# MAG3110_Breakout.net
KiCad netlist of a schematic drawn in EAGLE
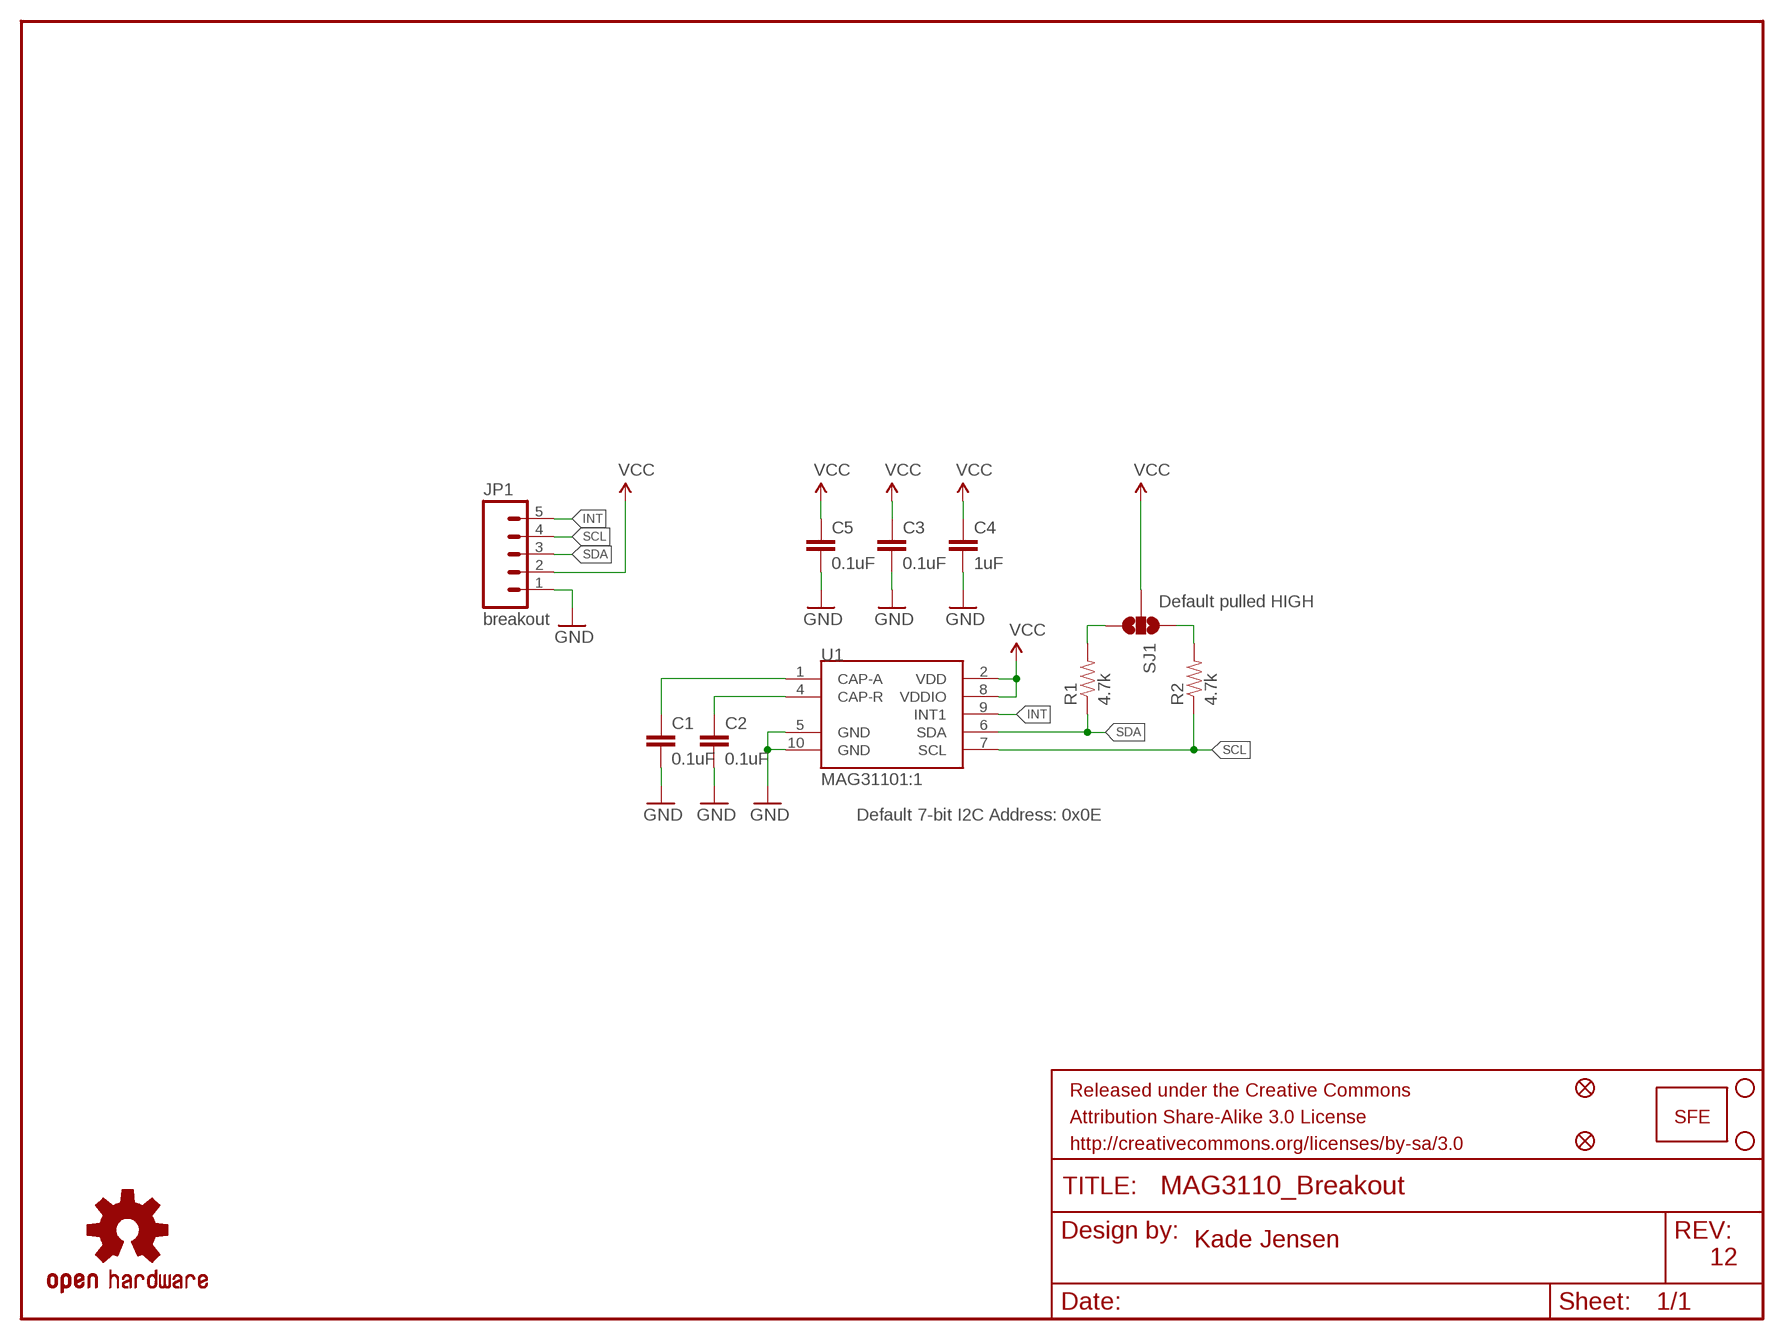
[diagram p0: schematic, sheet 1]

(export (version "E")
  (design (tool "Eeschema 10.0.6"))
  (components
    (comp (ref "C1")
      (value "0.1uF")
      (footprint "eagle-import:0603-CAP")
      (libsource (lib "eagle-import") (part "CAP0603-CAP"))
    )
    (comp (ref "C2")
      (value "0.1uF")
      (footprint "eagle-import:0603-CAP")
      (libsource (lib "eagle-import") (part "CAP0603-CAP"))
    )
    (comp (ref "C3")
      (value "0.1uF")
      (footprint "eagle-import:0603-CAP")
      (libsource (lib "eagle-import") (part "CAP0603-CAP"))
    )
    (comp (ref "C4")
      (value "1uF")
      (footprint "eagle-import:0603-CAP")
      (libsource (lib "eagle-import") (part "CAP0603-CAP"))
    )
    (comp (ref "C5")
      (value "0.1uF")
      (footprint "eagle-import:0603-CAP")
      (libsource (lib "eagle-import") (part "CAP0603-CAP"))
    )
    (comp (ref "FID1")
      (value "FIDUCIAL1X2")
      (footprint "eagle-import:FIDUCIAL-1X2")
      (libsource (lib "eagle-import") (part "FIDUCIAL1X2"))
    )
    (comp (ref "FID2")
      (value "FIDUCIAL1X2")
      (footprint "eagle-import:FIDUCIAL-1X2")
      (libsource (lib "eagle-import") (part "FIDUCIAL1X2"))
    )
    (comp (ref "FRAME2")
      (value "FRAME-LETTER")
      (footprint "eagle-import:CREATIVE_COMMONS")
      (libsource (lib "eagle-import") (part "FRAME-LETTER"))
    )
    (comp (ref "JP1")
      (value "breakout")
      (footprint "eagle-import:1X05")
      (libsource (lib "eagle-import") (part "M05PTH"))
    )
    (comp (ref "JP2")
      (value "STAND-OFF")
      (footprint "eagle-import:STAND-OFF")
      (libsource (lib "eagle-import") (part "STAND-OFF"))
    )
    (comp (ref "JP3")
      (value "STAND-OFF")
      (footprint "eagle-import:STAND-OFF")
      (libsource (lib "eagle-import") (part "STAND-OFF"))
    )
    (comp (ref "JP7")
      (value "LOGO-SFESK")
      (footprint "eagle-import:SFE-LOGO-FLAME")
      (libsource (lib "eagle-import") (part "LOGO-SFESK"))
    )
    (comp (ref "LOGO1")
      (value "OSHW-LOGOS")
      (footprint "eagle-import:OSHW-LOGO-S")
      (libsource (lib "eagle-import") (part "OSHW-LOGOS"))
    )
    (comp (ref "R1")
      (value "4.7k")
      (footprint "eagle-import:0603-RES")
      (libsource (lib "eagle-import") (part "RESISTOR0603-RES"))
    )
    (comp (ref "R2")
      (value "4.7k")
      (footprint "eagle-import:0603-RES")
      (libsource (lib "eagle-import") (part "RESISTOR0603-RES"))
    )
    (comp (ref "SJ1")
      (value "SOLDERJUMPER_2WAYPASTE1&2&3")
      (footprint "eagle-import:SJ_3_PASTE1&2&3")
      (libsource (lib "eagle-import") (part "SOLDERJUMPER_2WAYPASTE1&2&3"))
    )
    (comp (ref "U1")
      (value "MAG31101:1")
      (footprint "eagle-import:DFN-10-W")
      (libsource (lib "eagle-import") (part "MAG31101{colon}1"))
    )
  )
  (nets
    (net (code "1") (name "GND") (class "Default")
      (node (ref "C1") (pin "2") (pinfunction "2_2") (pintype "passive"))
      (node (ref "C2") (pin "2") (pinfunction "2_2") (pintype "passive"))
      (node (ref "C3") (pin "2") (pinfunction "2_2") (pintype "passive"))
      (node (ref "C4") (pin "2") (pinfunction "2_2") (pintype "passive"))
      (node (ref "C5") (pin "2") (pinfunction "2_2") (pintype "passive"))
      (node (ref "JP1") (pin "1") (pinfunction "1_1") (pintype "passive"))
      (node (ref "U1") (pin "10") (pinfunction "GND_10") (pintype "bidirectional"))
      (node (ref "U1") (pin "5") (pinfunction "GND_5") (pintype "bidirectional"))
    )
    (net (code "2") (name "INT") (class "Default")
      (node (ref "JP1") (pin "5") (pinfunction "5_5") (pintype "passive"))
      (node (ref "U1") (pin "9") (pinfunction "INT1_9") (pintype "bidirectional"))
    )
    (net (code "3") (name "Net-(R1-Pad2)") (class "Default")
      (node (ref "R1") (pin "2") (pinfunction "2_2") (pintype "passive"))
      (node (ref "SJ1") (pin "3") (pinfunction "3_3") (pintype "passive"))
    )
    (net (code "4") (name "Net-(R2-Pad2)") (class "Default")
      (node (ref "R2") (pin "2") (pinfunction "2_2") (pintype "passive"))
      (node (ref "SJ1") (pin "1") (pinfunction "1_1") (pintype "passive"))
    )
    (net (code "5") (name "Net-(U1-CAP-A)") (class "Default")
      (node (ref "C1") (pin "1") (pinfunction "1_1") (pintype "passive"))
      (node (ref "U1") (pin "1") (pinfunction "CAP-A_1") (pintype "bidirectional"))
    )
    (net (code "6") (name "Net-(U1-CAP-R)") (class "Default")
      (node (ref "C2") (pin "1") (pinfunction "1_1") (pintype "passive"))
      (node (ref "U1") (pin "4") (pinfunction "CAP-R_4") (pintype "bidirectional"))
    )
    (net (code "7") (name "SCL") (class "Default")
      (node (ref "JP1") (pin "4") (pinfunction "4_4") (pintype "passive"))
      (node (ref "R2") (pin "1") (pinfunction "1_1") (pintype "passive"))
      (node (ref "U1") (pin "7") (pinfunction "SCL_7") (pintype "bidirectional"))
    )
    (net (code "8") (name "SDA") (class "Default")
      (node (ref "JP1") (pin "3") (pinfunction "3_3") (pintype "passive"))
      (node (ref "R1") (pin "1") (pinfunction "1_1") (pintype "passive"))
      (node (ref "U1") (pin "6") (pinfunction "SDA_6") (pintype "bidirectional"))
    )
    (net (code "9") (name "VCC") (class "Default")
      (node (ref "C3") (pin "1") (pinfunction "1_1") (pintype "passive"))
      (node (ref "C4") (pin "1") (pinfunction "1_1") (pintype "passive"))
      (node (ref "C5") (pin "1") (pinfunction "1_1") (pintype "passive"))
      (node (ref "JP1") (pin "2") (pinfunction "2_2") (pintype "passive"))
      (node (ref "SJ1") (pin "2") (pinfunction "2_2") (pintype "passive"))
      (node (ref "U1") (pin "2") (pinfunction "VDD_2") (pintype "bidirectional"))
      (node (ref "U1") (pin "8") (pinfunction "VDDIO_8") (pintype "bidirectional"))
    )
  )
)
